# CanController.net
KiCad netlist of a schematic drawn in Altium Designer
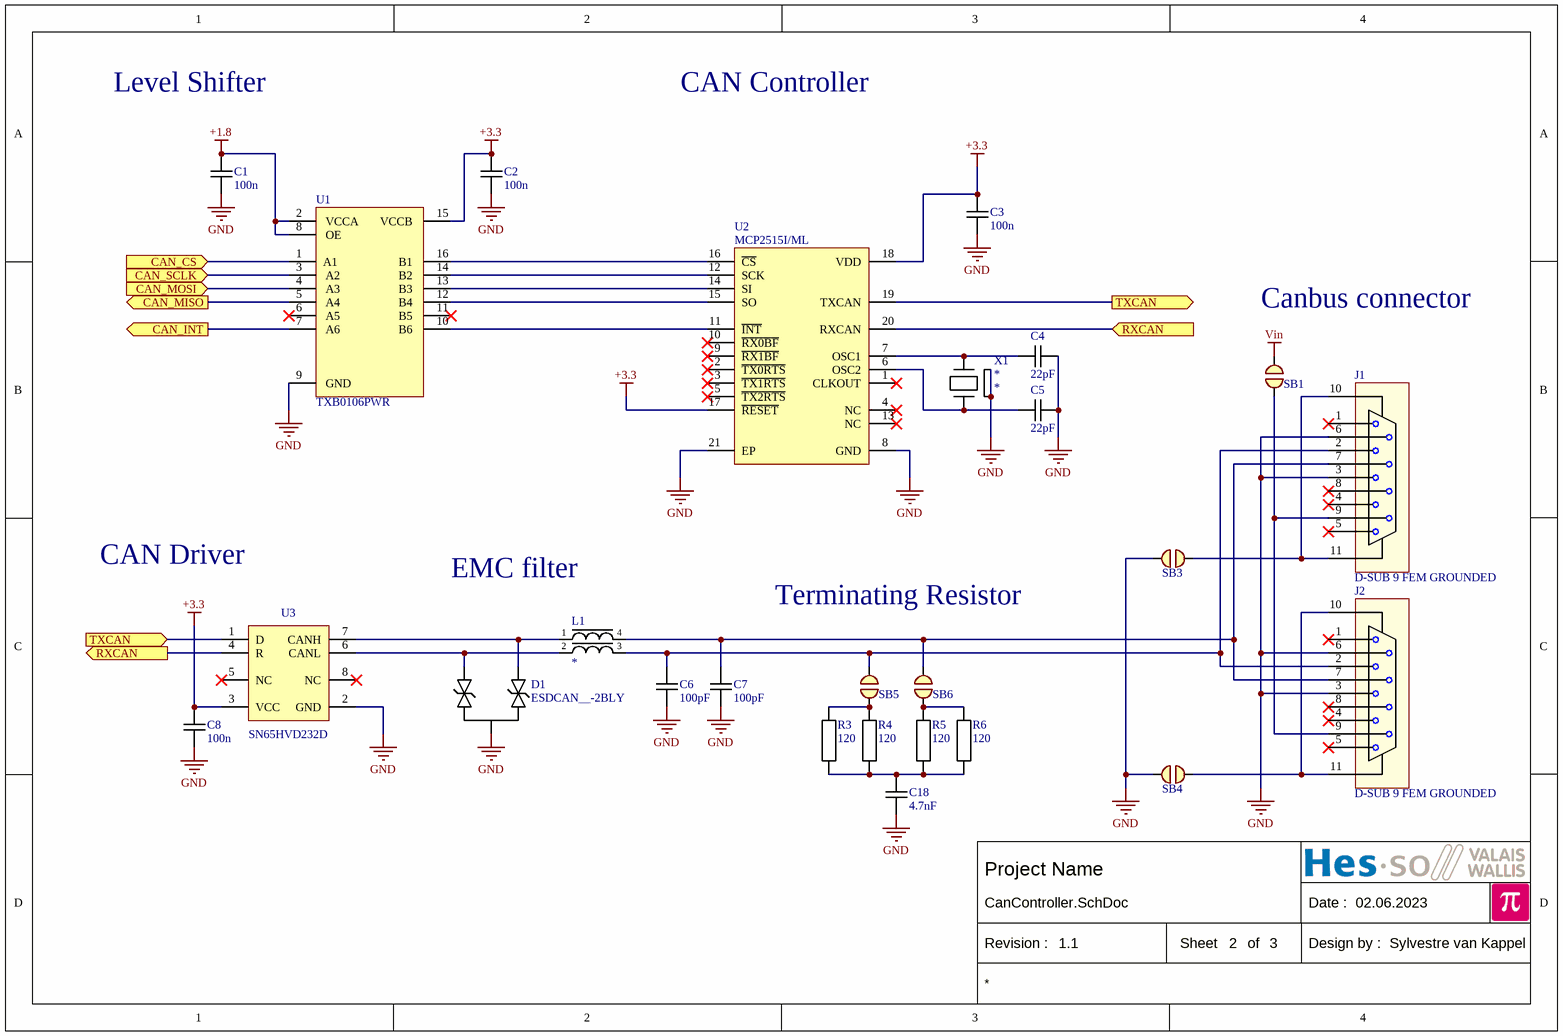
[diagram p0: CanController.SchDoc]

(export (version "E")
  (design (tool "Eeschema 10.0.6"))
  (components
    (comp (ref "C1")
      (value "100n")
      (footprint "CAPACITOR 1608 REFLOW")
      (description "Capacitor")
      (libsource (lib "Capacitor") (part "Capacitor"))
    )
    (comp (ref "C2")
      (value "100n")
      (footprint "CAPACITOR 1608 REFLOW")
      (description "Capacitor")
      (libsource (lib "Capacitor") (part "Capacitor"))
    )
    (comp (ref "C3")
      (value "100n")
      (footprint "CAPACITOR 1608 REFLOW")
      (description "Capacitor")
      (libsource (lib "Capacitor") (part "Capacitor"))
    )
    (comp (ref "C4")
      (value "22pF")
      (footprint "CAPACITOR 1608 REFLOW")
      (description "Capacitor")
      (libsource (lib "Capacitor") (part "Capacitor"))
    )
    (comp (ref "C5")
      (value "22pF")
      (footprint "CAPACITOR 1608 REFLOW")
      (description "Capacitor")
      (libsource (lib "Capacitor") (part "Capacitor"))
    )
    (comp (ref "C6")
      (value "100pF")
      (footprint "CAPACITOR 1608 REFLOW")
      (description "Capacitor")
      (libsource (lib "Capacitor") (part "Capacitor"))
    )
    (comp (ref "C7")
      (value "100pF")
      (footprint "CAPACITOR 1608 REFLOW")
      (description "Capacitor")
      (libsource (lib "Capacitor") (part "Capacitor"))
    )
    (comp (ref "C8")
      (value "100n")
      (footprint "CAPACITOR 1608 REFLOW")
      (description "Capacitor")
      (libsource (lib "Capacitor") (part "Capacitor"))
    )
    (comp (ref "C18")
      (value "4.7nF")
      (footprint "CAPACITOR 1608 REFLOW")
      (description "Capacitor")
      (libsource (lib "Capacitor") (part "Capacitor"))
    )
    (comp (ref "D1")
      (value "ESDCAN__-2BLY")
      (footprint "SOT23 P0.95 C1.6x3.0 H1.3")
      (description "Automotive dual-line TVS diode")
      (libsource (lib "Diode") (part "Diode ESDCAN__-2BLY"))
    )
    (comp (ref "J1")
      (value "D-SUB 9 FEM GROUNDED")
      (footprint "D-SUB 9 FEM Amphenol LD09S13A4GX00LF")
      (description "D-Subminiature 9 way Socket Right Angle")
      (libsource (lib "Connector") (part "D-SUB 9 FEM GROUNDED"))
    )
    (comp (ref "J2")
      (value "D-SUB 9 FEM GROUNDED")
      (footprint "D-SUB 9 FEM Amphenol LD09S13A4GX00LF")
      (description "D-Subminiature 9 way Socket Right Angle")
      (libsource (lib "Connector") (part "D-SUB 9 FEM GROUNDED"))
    )
    (comp (ref "L1")
      (value "*")
      (footprint "L CM 2X B82793C EPCOS")
      (description "Inductor Common Mode Filter")
      (libsource (lib "Inductor") (part "L CM 2X B82793C0 EPCOS"))
    )
    (comp (ref "R3")
      (value "120")
      (footprint "RESISTOR 1608 REFLOW")
      (description "Resistor")
      (libsource (lib "Resistor") (part "Resistor"))
    )
    (comp (ref "R4")
      (value "120")
      (footprint "RESISTOR 1608 REFLOW")
      (description "Resistor")
      (libsource (lib "Resistor") (part "Resistor"))
    )
    (comp (ref "R5")
      (value "120")
      (footprint "RESISTOR 1608 REFLOW")
      (description "Resistor")
      (libsource (lib "Resistor") (part "Resistor"))
    )
    (comp (ref "R6")
      (value "120")
      (footprint "RESISTOR 1608 REFLOW")
      (description "Resistor")
      (libsource (lib "Resistor") (part "Resistor"))
    )
    (comp (ref "SB1")
      (value "*")
      (footprint "Solder Bridge 1mm Unconnected")
      (description "Solderbridge Unconnected")
      (libsource (lib "Jumper") (part "Solderbridge Unconnected"))
    )
    (comp (ref "SB3")
      (value "*")
      (footprint "Solder Bridge 1mm Unconnected")
      (description "Solderbridge Unconnected")
      (libsource (lib "Jumper") (part "Solderbridge Unconnected"))
    )
    (comp (ref "SB4")
      (value "*")
      (footprint "Solder Bridge 1mm Unconnected")
      (description "Solderbridge Unconnected")
      (libsource (lib "Jumper") (part "Solderbridge Unconnected"))
    )
    (comp (ref "SB5")
      (value "*")
      (footprint "Solder Bridge 1mm Unconnected")
      (description "Solderbridge Unconnected")
      (libsource (lib "Jumper") (part "Solderbridge Unconnected"))
    )
    (comp (ref "SB6")
      (value "*")
      (footprint "Solder Bridge 1mm Unconnected")
      (description "Solderbridge Unconnected")
      (libsource (lib "Jumper") (part "Solderbridge Unconnected"))
    )
    (comp (ref "U1")
      (value "TXB0106PWR")
      (footprint "TSSOP16 P0.65 C5.0x4.5 H1.1")
      (libsource (lib "IntegratedCircuit") (part "TXB0106PWR"))
    )
    (comp (ref "U2")
      (value "MCP2515I/ML")
      (footprint "QFN20 P0.5 T2.05x2.05 C4.0x4.0 H0.85")
      (description "Stand-Alone CAN Controller with SPI Interface")
      (libsource (lib "IntegratedCircuit") (part "MCP2515I/ML"))
    )
    (comp (ref "U3")
      (value "SN65HVD232D")
      (footprint "SO8 P1.27 C4.0X5.0 H1.75")
      (description "CAN Bus Transceiver 3V3")
      (libsource (lib "IntegratedCircuit") (part "SN65HVD232D"))
    )
    (comp (ref "X1")
      (value "*")
      (footprint "CRYSTAL C3.2x2.5 Kyocera CX3225SB")
      (description "Crystal C3.2x2.5 Kyocera CX3225SB")
      (fields (field (name "ALTIUM_VALUE") "*"))
      (libsource (lib "Oscillator") (part "Crystal C3.2x2.5 Kyocera CX3225SB"))
    )
  )
  (nets
    (net (code "1") (name "+1.8") (class "Default")
      (node (ref "C1") (pin "2") (pinfunction "2_2") (pintype "passive"))
      (node (ref "U1") (pin "2") (pinfunction "VCCA_2") (pintype "passive"))
      (node (ref "U1") (pin "8") (pinfunction "OE_8") (pintype "passive"))
    )
    (net (code "2") (name "+3.3") (class "Default")
      (node (ref "C2") (pin "2") (pinfunction "2_2") (pintype "passive"))
      (node (ref "C3") (pin "2") (pinfunction "2_2") (pintype "passive"))
      (node (ref "C8") (pin "2") (pinfunction "2_2") (pintype "passive"))
      (node (ref "U1") (pin "15") (pinfunction "VCCB_15") (pintype "passive"))
      (node (ref "U2") (pin "17") (pinfunction "~{RESET}_17") (pintype "passive"))
      (node (ref "U2") (pin "18") (pinfunction "VDD_18") (pintype "passive"))
      (node (ref "U3") (pin "3") (pinfunction "VCC_3") (pintype "passive"))
    )
    (net (code "3") (name "/CAN_CS") (class "Default")
      (node (ref "U1") (pin "1") (pinfunction "A1_1") (pintype "passive"))
    )
    (net (code "4") (name "/CAN_INT") (class "Default")
      (node (ref "U1") (pin "7") (pinfunction "A6_7") (pintype "passive"))
    )
    (net (code "5") (name "/CAN_MISO") (class "Default")
      (node (ref "U1") (pin "5") (pinfunction "A4_5") (pintype "passive"))
    )
    (net (code "6") (name "/CAN_MOSI") (class "Default")
      (node (ref "U1") (pin "4") (pinfunction "A3_4") (pintype "passive"))
    )
    (net (code "7") (name "/CAN_SCLK") (class "Default")
      (node (ref "U1") (pin "3") (pinfunction "A2_3") (pintype "passive"))
    )
    (net (code "8") (name "/RXCAN") (class "Default")
      (node (ref "U2") (pin "20") (pinfunction "RXCAN_20") (pintype "passive"))
      (node (ref "U3") (pin "4") (pinfunction "R_4") (pintype "passive"))
    )
    (net (code "9") (name "/TXCAN") (class "Default")
      (node (ref "U2") (pin "19") (pinfunction "TXCAN_19") (pintype "passive"))
      (node (ref "U3") (pin "1") (pinfunction "D_1") (pintype "passive"))
    )
    (net (code "10") (name "GND") (class "Default")
      (node (ref "C1") (pin "1") (pinfunction "1_1") (pintype "passive"))
      (node (ref "C18") (pin "1") (pinfunction "1_1") (pintype "passive"))
      (node (ref "C2") (pin "1") (pinfunction "1_1") (pintype "passive"))
      (node (ref "C3") (pin "1") (pinfunction "1_1") (pintype "passive"))
      (node (ref "C4") (pin "1") (pinfunction "1_1") (pintype "passive"))
      (node (ref "C5") (pin "1") (pinfunction "1_1") (pintype "passive"))
      (node (ref "C6") (pin "1") (pinfunction "1_1") (pintype "passive"))
      (node (ref "C7") (pin "1") (pinfunction "1_1") (pintype "passive"))
      (node (ref "C8") (pin "1") (pinfunction "1_1") (pintype "passive"))
      (node (ref "D1") (pin "3") (pinfunction "COM_3") (pintype "passive"))
      (node (ref "J1") (pin "3") (pintype "passive"))
      (node (ref "J1") (pin "6") (pintype "passive"))
      (node (ref "J2") (pin "3") (pintype "passive"))
      (node (ref "J2") (pin "6") (pintype "passive"))
      (node (ref "SB3") (pin "1") (pinfunction "0_1") (pintype "passive"))
      (node (ref "SB4") (pin "1") (pinfunction "0_1") (pintype "passive"))
      (node (ref "U1") (pin "9") (pinfunction "GND_9") (pintype "passive"))
      (node (ref "U2") (pin "21") (pinfunction "EP_21") (pintype "passive"))
      (node (ref "U2") (pin "8") (pinfunction "GND_8") (pintype "passive"))
      (node (ref "U3") (pin "2") (pinfunction "GND_2") (pintype "passive"))
      (node (ref "X1") (pin "2") (pinfunction "2_2") (pintype "passive"))
      (node (ref "X1") (pin "4") (pinfunction "4_4") (pintype "passive"))
    )
    (net (code "11") (name "Net-(C18-Pad2)") (class "Default")
      (node (ref "C18") (pin "2") (pinfunction "2_2") (pintype "passive"))
      (node (ref "R3") (pin "1") (pinfunction "1_1") (pintype "passive"))
      (node (ref "R4") (pin "1") (pinfunction "1_1") (pintype "passive"))
      (node (ref "R5") (pin "1") (pinfunction "1_1") (pintype "passive"))
      (node (ref "R6") (pin "1") (pinfunction "1_1") (pintype "passive"))
    )
    (net (code "12") (name "Net-(D1-A1)") (class "Default")
      (node (ref "D1") (pin "1") (pinfunction "A1_1") (pintype "passive"))
      (node (ref "L1") (pin "1") (pinfunction "1_1") (pintype "passive"))
      (node (ref "U3") (pin "7") (pinfunction "CANH_7") (pintype "passive"))
    )
    (net (code "13") (name "Net-(D1-C2)") (class "Default")
      (node (ref "D1") (pin "2") (pinfunction "C2_2") (pintype "passive"))
      (node (ref "L1") (pin "2") (pinfunction "2_2") (pintype "passive"))
      (node (ref "U3") (pin "6") (pinfunction "CANL_6") (pintype "passive"))
    )
    (net (code "14") (name "Net-(SB1-1)") (class "Default")
      (node (ref "J1") (pin "9") (pintype "passive"))
      (node (ref "J2") (pin "9") (pintype "passive"))
      (node (ref "SB1") (pin "2") (pinfunction "1_2") (pintype "passive"))
    )
    (net (code "15") (name "Net-(SB3-1)") (class "Default")
      (node (ref "J1") (pin "10") (pintype "passive"))
      (node (ref "J1") (pin "11") (pintype "passive"))
      (node (ref "SB3") (pin "2") (pinfunction "1_2") (pintype "passive"))
    )
    (net (code "16") (name "Net-(SB4-1)") (class "Default")
      (node (ref "J2") (pin "10") (pintype "passive"))
      (node (ref "J2") (pin "11") (pintype "passive"))
      (node (ref "SB4") (pin "2") (pinfunction "1_2") (pintype "passive"))
    )
    (net (code "17") (name "Net-(SB5-0)") (class "Default")
      (node (ref "R3") (pin "2") (pinfunction "2_2") (pintype "passive"))
      (node (ref "R4") (pin "2") (pinfunction "2_2") (pintype "passive"))
      (node (ref "SB5") (pin "1") (pinfunction "0_1") (pintype "passive"))
    )
    (net (code "18") (name "Net-(SB5-1)") (class "Default")
      (node (ref "C6") (pin "2") (pinfunction "2_2") (pintype "passive"))
      (node (ref "J1") (pin "2") (pintype "passive"))
      (node (ref "J2") (pin "2") (pintype "passive"))
      (node (ref "L1") (pin "3") (pinfunction "3_3") (pintype "passive"))
      (node (ref "SB5") (pin "2") (pinfunction "1_2") (pintype "passive"))
    )
    (net (code "19") (name "Net-(SB6-0)") (class "Default")
      (node (ref "R5") (pin "2") (pinfunction "2_2") (pintype "passive"))
      (node (ref "R6") (pin "2") (pinfunction "2_2") (pintype "passive"))
      (node (ref "SB6") (pin "1") (pinfunction "0_1") (pintype "passive"))
    )
    (net (code "20") (name "Net-(SB6-1)") (class "Default")
      (node (ref "C7") (pin "2") (pinfunction "2_2") (pintype "passive"))
      (node (ref "J1") (pin "7") (pintype "passive"))
      (node (ref "J2") (pin "7") (pintype "passive"))
      (node (ref "L1") (pin "4") (pinfunction "4_4") (pintype "passive"))
      (node (ref "SB6") (pin "2") (pinfunction "1_2") (pintype "passive"))
    )
    (net (code "21") (name "Net-(U1-B1)") (class "Default")
      (node (ref "U1") (pin "16") (pinfunction "B1_16") (pintype "passive"))
      (node (ref "U2") (pin "16") (pinfunction "~{CS}_16") (pintype "passive"))
    )
    (net (code "22") (name "Net-(U1-B2)") (class "Default")
      (node (ref "U1") (pin "14") (pinfunction "B2_14") (pintype "passive"))
      (node (ref "U2") (pin "12") (pinfunction "SCK_12") (pintype "passive"))
    )
    (net (code "23") (name "Net-(U1-B3)") (class "Default")
      (node (ref "U1") (pin "13") (pinfunction "B3_13") (pintype "passive"))
      (node (ref "U2") (pin "14") (pinfunction "SI_14") (pintype "passive"))
    )
    (net (code "24") (name "Net-(U1-B4)") (class "Default")
      (node (ref "U1") (pin "12") (pinfunction "B4_12") (pintype "passive"))
      (node (ref "U2") (pin "15") (pinfunction "SO_15") (pintype "passive"))
    )
    (net (code "25") (name "Net-(U1-B6)") (class "Default")
      (node (ref "U1") (pin "10") (pinfunction "B6_10") (pintype "passive"))
      (node (ref "U2") (pin "11") (pinfunction "~{INT}_11") (pintype "passive"))
    )
    (net (code "26") (name "Net-(U2-OSC1)") (class "Default")
      (node (ref "C4") (pin "2") (pinfunction "2_2") (pintype "passive"))
      (node (ref "U2") (pin "7") (pinfunction "OSC1_7") (pintype "passive"))
      (node (ref "X1") (pin "3") (pinfunction "3_3") (pintype "passive"))
    )
    (net (code "27") (name "Net-(U2-OSC2)") (class "Default")
      (node (ref "C5") (pin "2") (pinfunction "2_2") (pintype "passive"))
      (node (ref "U2") (pin "6") (pinfunction "OSC2_6") (pintype "passive"))
      (node (ref "X1") (pin "1") (pinfunction "1_1") (pintype "passive"))
    )
    (net (code "28") (name "Vin") (class "Default")
      (node (ref "SB1") (pin "1") (pinfunction "0_1") (pintype "passive"))
    )
    (net (code "29") (name "unconnected-(J1-Pad1)") (class "Default")
      (node (ref "J1") (pin "1") (pintype "passive+no_connect"))
    )
    (net (code "30") (name "unconnected-(J1-Pad4)") (class "Default")
      (node (ref "J1") (pin "4") (pintype "passive+no_connect"))
    )
    (net (code "31") (name "unconnected-(J1-Pad5)") (class "Default")
      (node (ref "J1") (pin "5") (pintype "passive+no_connect"))
    )
    (net (code "32") (name "unconnected-(J1-Pad8)") (class "Default")
      (node (ref "J1") (pin "8") (pintype "passive+no_connect"))
    )
    (net (code "33") (name "unconnected-(J2-Pad1)") (class "Default")
      (node (ref "J2") (pin "1") (pintype "passive+no_connect"))
    )
    (net (code "34") (name "unconnected-(J2-Pad4)") (class "Default")
      (node (ref "J2") (pin "4") (pintype "passive+no_connect"))
    )
    (net (code "35") (name "unconnected-(J2-Pad5)") (class "Default")
      (node (ref "J2") (pin "5") (pintype "passive+no_connect"))
    )
    (net (code "36") (name "unconnected-(J2-Pad8)") (class "Default")
      (node (ref "J2") (pin "8") (pintype "passive+no_connect"))
    )
    (net (code "37") (name "unconnected-(U1-A5-Pad6)") (class "Default")
      (node (ref "U1") (pin "6") (pinfunction "A5_6") (pintype "passive+no_connect"))
    )
    (net (code "38") (name "unconnected-(U1-B5-Pad11)") (class "Default")
      (node (ref "U1") (pin "11") (pinfunction "B5_11") (pintype "passive+no_connect"))
    )
    (net (code "39") (name "unconnected-(U2-CLKOUT-Pad1)") (class "Default")
      (node (ref "U2") (pin "1") (pinfunction "CLKOUT_1") (pintype "passive+no_connect"))
    )
    (net (code "40") (name "unconnected-(U2-NC-Pad4)") (class "Default")
      (node (ref "U2") (pin "4") (pinfunction "NC_4") (pintype "passive+no_connect"))
    )
    (net (code "41") (name "unconnected-(U2-NC-Pad13)") (class "Default")
      (node (ref "U2") (pin "13") (pinfunction "NC_13") (pintype "passive+no_connect"))
    )
    (net (code "42") (name "unconnected-(U2-~{RX0BF}-Pad10)") (class "Default")
      (node (ref "U2") (pin "10") (pinfunction "~{RX0BF}_10") (pintype "passive+no_connect"))
    )
    (net (code "43") (name "unconnected-(U2-~{RX1BF}-Pad9)") (class "Default")
      (node (ref "U2") (pin "9") (pinfunction "~{RX1BF}_9") (pintype "passive+no_connect"))
    )
    (net (code "44") (name "unconnected-(U2-~{TX0RTS}-Pad2)") (class "Default")
      (node (ref "U2") (pin "2") (pinfunction "~{TX0RTS}_2") (pintype "passive+no_connect"))
    )
    (net (code "45") (name "unconnected-(U2-~{TX1RTS}-Pad3)") (class "Default")
      (node (ref "U2") (pin "3") (pinfunction "~{TX1RTS}_3") (pintype "passive+no_connect"))
    )
    (net (code "46") (name "unconnected-(U2-~{TX2RTS}-Pad5)") (class "Default")
      (node (ref "U2") (pin "5") (pinfunction "~{TX2RTS}_5") (pintype "passive+no_connect"))
    )
    (net (code "47") (name "unconnected-(U3-NC-Pad5)") (class "Default")
      (node (ref "U3") (pin "5") (pinfunction "NC_5") (pintype "passive+no_connect"))
    )
    (net (code "48") (name "unconnected-(U3-NC-Pad8)") (class "Default")
      (node (ref "U3") (pin "8") (pinfunction "NC_8") (pintype "passive+no_connect"))
    )
  )
)
